# dmx_noConn.net
KiCad netlist of a schematic drawn in EAGLE
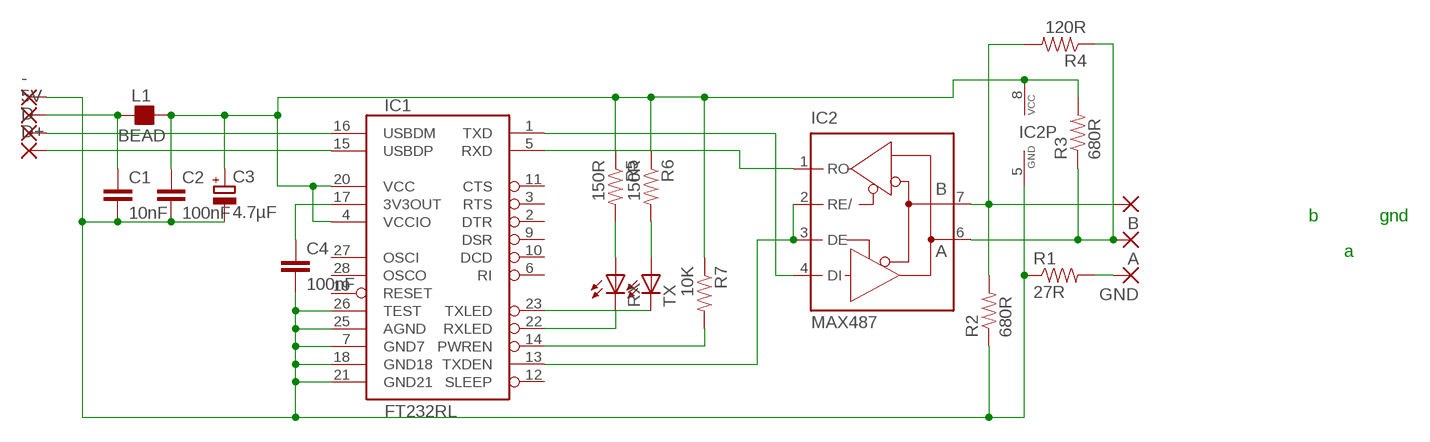
[diagram p0: schematic, sheet 1]

(export (version "E")
  (design (tool "Eeschema 10.0.6"))
  (components
    (comp (ref "-")
      (value "SMD5")
      (footprint "eagle-import:SMD2,54-5,08")
      (libsource (lib "eagle-import") (part "SMD5"))
    )
    (comp (ref "5V")
      (value "SMD5")
      (footprint "eagle-import:SMD2,54-5,08")
      (libsource (lib "eagle-import") (part "SMD5"))
    )
    (comp (ref "A")
      (value "SMD5")
      (footprint "eagle-import:SMD2,54-5,08")
      (libsource (lib "eagle-import") (part "SMD5"))
    )
    (comp (ref "B")
      (value "SMD5")
      (footprint "eagle-import:SMD2,54-5,08")
      (libsource (lib "eagle-import") (part "SMD5"))
    )
    (comp (ref "C1")
      (value "10nF")
      (footprint "eagle-import:0805")
      (libsource (lib "eagle-import") (part "CAP0805"))
    )
    (comp (ref "C2")
      (value "100nF")
      (footprint "eagle-import:0805")
      (libsource (lib "eagle-import") (part "CAP0805"))
    )
    (comp (ref "C3")
      (value "4.7µF")
      (footprint "eagle-import:SMC_C")
      (libsource (lib "eagle-import") (part "CPOL-EUSMCC"))
    )
    (comp (ref "C4")
      (value "100nF")
      (footprint "eagle-import:0805")
      (libsource (lib "eagle-import") (part "CAP0805"))
    )
    (comp (ref "D+")
      (value "SMD5")
      (footprint "eagle-import:SMD2,54-5,08")
      (libsource (lib "eagle-import") (part "SMD5"))
    )
    (comp (ref "D-")
      (value "SMD5")
      (footprint "eagle-import:SMD2,54-5,08")
      (libsource (lib "eagle-import") (part "SMD5"))
    )
    (comp (ref "GND")
      (value "SMD5")
      (footprint "eagle-import:SMD2,54-5,08")
      (libsource (lib "eagle-import") (part "SMD5"))
    )
    (comp (ref "IC1")
      (value "FT232RL")
      (footprint "eagle-import:SSOP28DB")
      (libsource (lib "eagle-import") (part "FT232RLSSOP"))
    )
    (comp (ref "IC2")
      (value "MAX487")
      (footprint "eagle-import:SO08")
      (fields (field (name "MF") "MAXIM") (field (name "MPN") "MAX481CSA"))
      (libsource (lib "eagle-import") (part "MAX481CSA"))
    )
    (comp (ref "L1")
      (value "BEAD")
      (footprint "eagle-import:L0805")
      (libsource (lib "eagle-import") (part "FB_0805"))
    )
    (comp (ref "R1")
      (value "27R")
      (footprint "eagle-import:0805")
      (libsource (lib "eagle-import") (part "RESISTOR0805-RES"))
    )
    (comp (ref "R2")
      (value "680R")
      (footprint "eagle-import:0805")
      (libsource (lib "eagle-import") (part "RESISTOR0805-RES"))
    )
    (comp (ref "R3")
      (value "680R")
      (footprint "eagle-import:0805")
      (libsource (lib "eagle-import") (part "RESISTOR0805-RES"))
    )
    (comp (ref "R4")
      (value "120R")
      (footprint "eagle-import:0805")
      (libsource (lib "eagle-import") (part "RESISTOR0805-RES"))
    )
    (comp (ref "R5")
      (value "150R")
      (footprint "eagle-import:0805")
      (libsource (lib "eagle-import") (part "RESISTOR0805-RES"))
    )
    (comp (ref "R6")
      (value "150R")
      (footprint "eagle-import:0805")
      (libsource (lib "eagle-import") (part "RESISTOR0805-RES"))
    )
    (comp (ref "R7")
      (value "10K")
      (footprint "eagle-import:0805")
      (libsource (lib "eagle-import") (part "RESISTOR0805-RES"))
    )
    (comp (ref "RX")
      (value "LEDCHIP-LED0805")
      (footprint "eagle-import:CHIP-LED0805")
      (libsource (lib "eagle-import") (part "LEDCHIP-LED0805"))
    )
    (comp (ref "TX")
      (value "LEDCHIP-LED0805")
      (footprint "eagle-import:CHIP-LED0805")
      (libsource (lib "eagle-import") (part "LEDCHIP-LED0805"))
    )
  )
  (nets
    (net (code "1") (name "Net-(--P)") (class "Default")
      (node (ref "-") (pin "1") (pinfunction "P_1") (pintype "passive"))
      (node (ref "C1") (pin "2") (pinfunction "2_2") (pintype "passive"))
      (node (ref "C2") (pin "2") (pinfunction "2_2") (pintype "passive"))
      (node (ref "C3") (pin "-") (pinfunction "-_-") (pintype "passive"))
      (node (ref "C4") (pin "2") (pinfunction "2_2") (pintype "passive"))
      (node (ref "IC1") (pin "18") (pinfunction "GND18_18") (pintype "power_in"))
      (node (ref "IC1") (pin "21") (pinfunction "GND21_21") (pintype "power_in"))
      (node (ref "IC1") (pin "25") (pinfunction "AGND_25") (pintype "power_in"))
      (node (ref "IC1") (pin "26") (pinfunction "TEST_26") (pintype "input"))
      (node (ref "IC1") (pin "7") (pinfunction "GND7_7") (pintype "power_in"))
      (node (ref "IC2") (pin "5") (pinfunction "GND_5") (pintype "power_in"))
      (node (ref "R1") (pin "1") (pinfunction "1_1") (pintype "passive"))
      (node (ref "R2") (pin "1") (pinfunction "1_1") (pintype "passive"))
    )
    (net (code "2") (name "Net-(5V-P)") (class "Default")
      (node (ref "5V") (pin "1") (pinfunction "P_1") (pintype "passive"))
      (node (ref "C1") (pin "1") (pinfunction "1_1") (pintype "passive"))
      (node (ref "L1") (pin "1") (pinfunction "1_1") (pintype "passive"))
    )
    (net (code "3") (name "Net-(A-P)") (class "Default")
      (node (ref "A") (pin "1") (pinfunction "P_1") (pintype "passive"))
      (node (ref "IC2") (pin "6") (pinfunction "A_6") (pintype "passive"))
      (node (ref "R3") (pin "1") (pinfunction "1_1") (pintype "passive"))
      (node (ref "R4") (pin "1") (pinfunction "1_1") (pintype "passive"))
    )
    (net (code "4") (name "Net-(B-P)") (class "Default")
      (node (ref "B") (pin "1") (pinfunction "P_1") (pintype "passive"))
      (node (ref "IC2") (pin "7") (pinfunction "B_7") (pintype "passive"))
      (node (ref "R2") (pin "2") (pinfunction "2_2") (pintype "passive"))
      (node (ref "R4") (pin "2") (pinfunction "2_2") (pintype "passive"))
    )
    (net (code "5") (name "Net-(D+-P)") (class "Default")
      (node (ref "D+") (pin "1") (pinfunction "P_1") (pintype "passive"))
      (node (ref "IC1") (pin "15") (pinfunction "USBDP_15") (pintype "bidirectional"))
    )
    (net (code "6") (name "Net-(D--P)") (class "Default")
      (node (ref "D-") (pin "1") (pinfunction "P_1") (pintype "passive"))
      (node (ref "IC1") (pin "16") (pinfunction "USBDM_16") (pintype "bidirectional"))
    )
    (net (code "7") (name "Net-(GND-P)") (class "Default")
      (node (ref "GND") (pin "1") (pinfunction "P_1") (pintype "passive"))
      (node (ref "R1") (pin "2") (pinfunction "2_2") (pintype "passive"))
    )
    (net (code "8") (name "Net-(IC1-3V3OUT)") (class "Default")
      (node (ref "C4") (pin "1") (pinfunction "1_1") (pintype "passive"))
      (node (ref "IC1") (pin "17") (pinfunction "3V3OUT_17") (pintype "output"))
    )
    (net (code "9") (name "Net-(IC1-PWREN)") (class "Default")
      (node (ref "IC1") (pin "14") (pinfunction "PWREN_14") (pintype "input"))
      (node (ref "R7") (pin "2") (pinfunction "2_2") (pintype "passive"))
    )
    (net (code "10") (name "Net-(IC1-RXD)") (class "Default")
      (node (ref "IC1") (pin "5") (pinfunction "RXD_5") (pintype "input"))
      (node (ref "IC2") (pin "1") (pinfunction "RO_1") (pintype "output"))
    )
    (net (code "11") (name "Net-(IC1-RXLED)") (class "Default")
      (node (ref "IC1") (pin "22") (pinfunction "RXLED_22") (pintype "input"))
      (node (ref "RX") (pin "C") (pinfunction "C_C") (pintype "passive"))
    )
    (net (code "12") (name "Net-(IC1-TXD)") (class "Default")
      (node (ref "IC1") (pin "1") (pinfunction "TXD_1") (pintype "output"))
      (node (ref "IC2") (pin "4") (pinfunction "DI_4") (pintype "input"))
    )
    (net (code "13") (name "Net-(IC1-TXDEN)") (class "Default")
      (node (ref "IC1") (pin "13") (pinfunction "TXDEN_13") (pintype "input"))
      (node (ref "IC2") (pin "2") (pinfunction "RE/_2") (pintype "input"))
      (node (ref "IC2") (pin "3") (pinfunction "DE_3") (pintype "input"))
    )
    (net (code "14") (name "Net-(IC1-TXLED)") (class "Default")
      (node (ref "IC1") (pin "23") (pinfunction "TXLED_23") (pintype "input"))
      (node (ref "TX") (pin "C") (pinfunction "C_C") (pintype "passive"))
    )
    (net (code "15") (name "Net-(IC1-VCC)") (class "Default")
      (node (ref "C2") (pin "1") (pinfunction "1_1") (pintype "passive"))
      (node (ref "C3") (pin "+") (pinfunction "+_+") (pintype "passive"))
      (node (ref "IC1") (pin "20") (pinfunction "VCC_20") (pintype "power_in"))
      (node (ref "IC1") (pin "4") (pinfunction "VCCIO_4") (pintype "power_in"))
      (node (ref "IC2") (pin "8") (pinfunction "VCC_8") (pintype "power_in"))
      (node (ref "L1") (pin "2") (pinfunction "2_2") (pintype "passive"))
      (node (ref "R3") (pin "2") (pinfunction "2_2") (pintype "passive"))
      (node (ref "R5") (pin "1") (pinfunction "1_1") (pintype "passive"))
      (node (ref "R6") (pin "1") (pinfunction "1_1") (pintype "passive"))
      (node (ref "R7") (pin "1") (pinfunction "1_1") (pintype "passive"))
    )
    (net (code "16") (name "Net-(R5-Pad2)") (class "Default")
      (node (ref "R5") (pin "2") (pinfunction "2_2") (pintype "passive"))
      (node (ref "RX") (pin "A") (pinfunction "A_A") (pintype "passive"))
    )
    (net (code "17") (name "Net-(R6-Pad2)") (class "Default")
      (node (ref "R6") (pin "2") (pinfunction "2_2") (pintype "passive"))
      (node (ref "TX") (pin "A") (pinfunction "A_A") (pintype "passive"))
    )
    (net (code "18") (name "unconnected-(IC1-CTS-Pad11)") (class "Default")
      (node (ref "IC1") (pin "11") (pinfunction "CTS_11") (pintype "input"))
    )
    (net (code "19") (name "unconnected-(IC1-DCD-Pad10)") (class "Default")
      (node (ref "IC1") (pin "10") (pinfunction "DCD_10") (pintype "input"))
    )
    (net (code "20") (name "unconnected-(IC1-DSR-Pad9)") (class "Default")
      (node (ref "IC1") (pin "9") (pinfunction "DSR_9") (pintype "input"))
    )
    (net (code "21") (name "unconnected-(IC1-DTR-Pad2)") (class "Default")
      (node (ref "IC1") (pin "2") (pinfunction "DTR_2") (pintype "output"))
    )
    (net (code "22") (name "unconnected-(IC1-OSCI-Pad27)") (class "Default")
      (node (ref "IC1") (pin "27") (pinfunction "OSCI_27") (pintype "input"))
    )
    (net (code "23") (name "unconnected-(IC1-OSCO-Pad28)") (class "Default")
      (node (ref "IC1") (pin "28") (pinfunction "OSCO_28") (pintype "output"))
    )
    (net (code "24") (name "unconnected-(IC1-RESET-Pad19)") (class "Default")
      (node (ref "IC1") (pin "19") (pinfunction "RESET_19") (pintype "input"))
    )
    (net (code "25") (name "unconnected-(IC1-RI-Pad6)") (class "Default")
      (node (ref "IC1") (pin "6") (pinfunction "RI_6") (pintype "input"))
    )
    (net (code "26") (name "unconnected-(IC1-RTS-Pad3)") (class "Default")
      (node (ref "IC1") (pin "3") (pinfunction "RTS_3") (pintype "output"))
    )
    (net (code "27") (name "unconnected-(IC1-SLEEP-Pad12)") (class "Default")
      (node (ref "IC1") (pin "12") (pinfunction "SLEEP_12") (pintype "input"))
    )
  )
)
